# test2.net
KiCad netlist of a schematic drawn in EAGLE
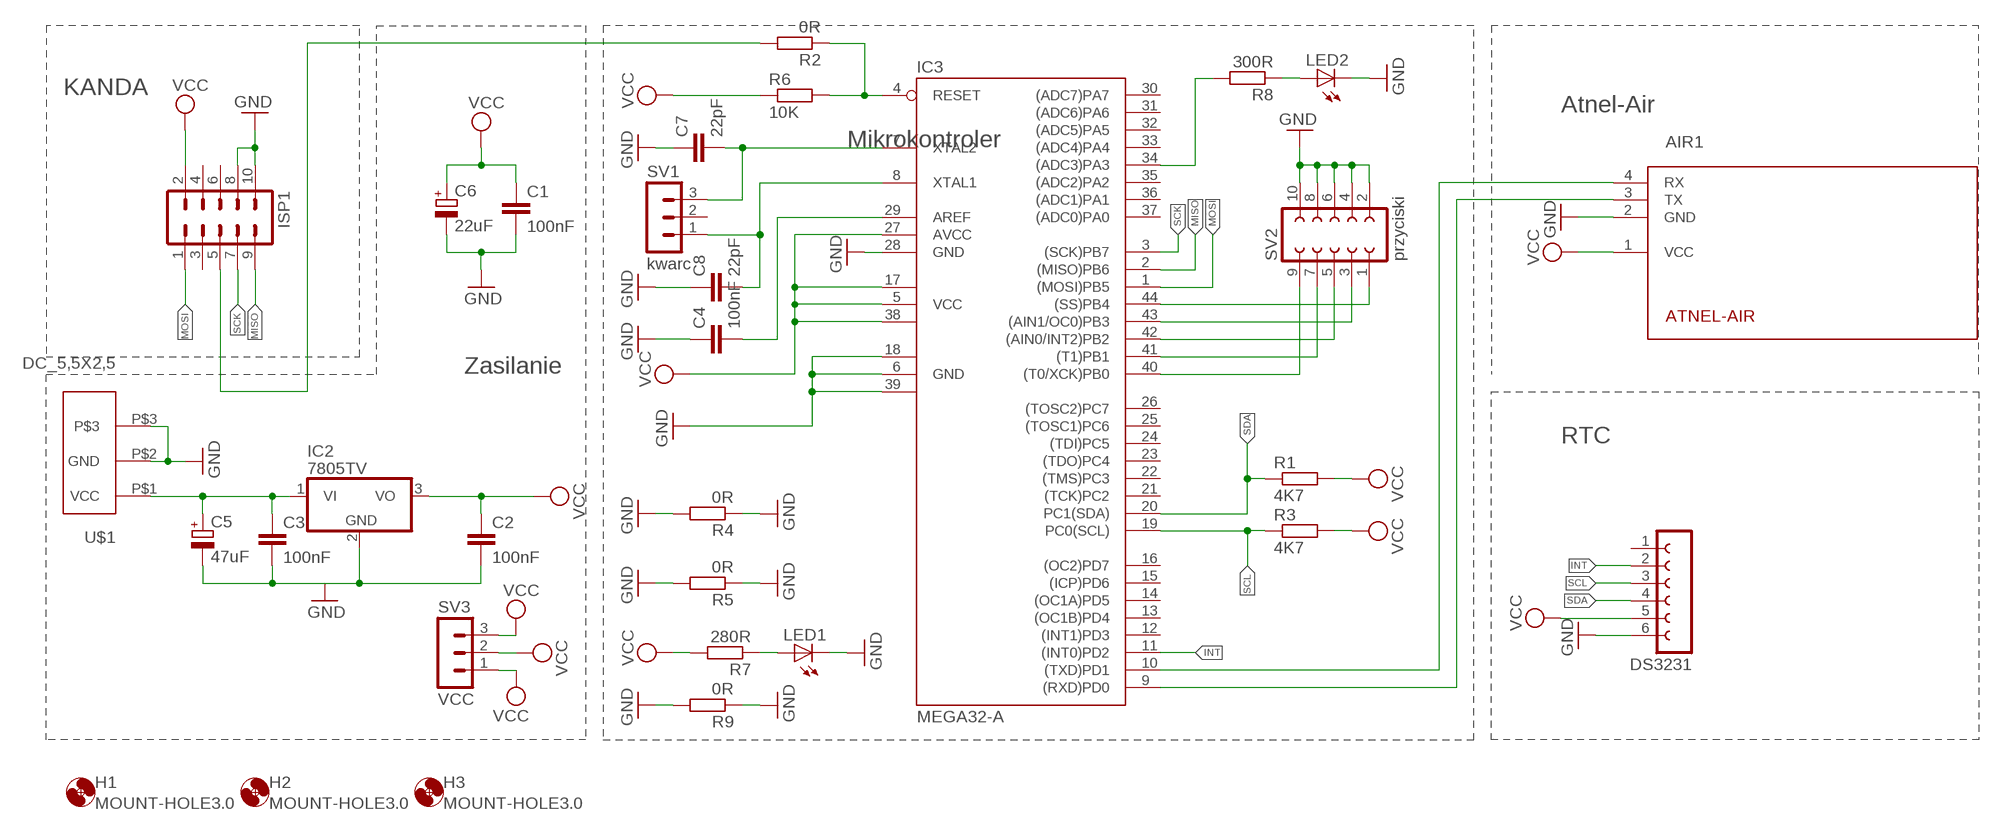
[diagram p0: schematic, sheet 1]

(export (version "E")
  (design (tool "Eeschema 10.0.6"))
  (components
    (comp (ref "AIR1")
      (value "ATNEL-AIR")
      (footprint "eagle-import:ATNEL-AIR")
      (libsource (lib "eagle-import") (part "ATNEL-AIR"))
    )
    (comp (ref "C1")
      (value "100nF")
      (footprint "eagle-import:C025-024X044")
      (libsource (lib "eagle-import") (part "C-EU025-024X044"))
    )
    (comp (ref "C2")
      (value "100nF")
      (footprint "eagle-import:C025-024X044")
      (libsource (lib "eagle-import") (part "C-EU025-024X044"))
    )
    (comp (ref "C3")
      (value "100nF")
      (footprint "eagle-import:C025-024X044")
      (libsource (lib "eagle-import") (part "C-EU025-024X044"))
    )
    (comp (ref "C4")
      (value "100nF")
      (footprint "eagle-import:C025-024X044")
      (libsource (lib "eagle-import") (part "C-EU025-024X044"))
    )
    (comp (ref "C5")
      (value "47uF")
      (footprint "eagle-import:B45181A")
      (libsource (lib "eagle-import") (part "CPOL-EUB45181A"))
    )
    (comp (ref "C6")
      (value "22uF")
      (footprint "eagle-import:B45181A")
      (libsource (lib "eagle-import") (part "CPOL-EUB45181A"))
    )
    (comp (ref "C7")
      (value "22pF")
      (footprint "eagle-import:C025-024X044")
      (libsource (lib "eagle-import") (part "C-EU025-024X044"))
    )
    (comp (ref "C8")
      (value "22pF")
      (footprint "eagle-import:C025-024X044")
      (libsource (lib "eagle-import") (part "C-EU025-024X044"))
    )
    (comp (ref "DS3231")
      (value "FE06-1")
      (footprint "eagle-import:FE06")
      (libsource (lib "eagle-import") (part "FE06-1"))
    )
    (comp (ref "H1")
      (value "MOUNT-HOLE3.0")
      (footprint "eagle-import:3,0")
      (libsource (lib "eagle-import") (part "MOUNT-HOLE3.0"))
    )
    (comp (ref "H2")
      (value "MOUNT-HOLE3.0")
      (footprint "eagle-import:3,0")
      (libsource (lib "eagle-import") (part "MOUNT-HOLE3.0"))
    )
    (comp (ref "H3")
      (value "MOUNT-HOLE3.0")
      (footprint "eagle-import:3,0")
      (libsource (lib "eagle-import") (part "MOUNT-HOLE3.0"))
    )
    (comp (ref "IC2")
      (value "7805TV")
      (footprint "eagle-import:TO220V")
      (libsource (lib "eagle-import") (part "78TV05"))
    )
    (comp (ref "IC3")
      (value "MEGA32-A")
      (footprint "eagle-import:TQFP44")
      (fields (field (name "MPN") "ATMEGA32-16AU"))
      (libsource (lib "eagle-import") (part "MEGA32-A"))
    )
    (comp (ref "ISP1")
      (value "ML10")
      (footprint "eagle-import:ML10")
      (libsource (lib "eagle-import") (part "ML10"))
    )
    (comp (ref "LED1")
      (value "LED5MM")
      (footprint "eagle-import:LED5MM")
      (libsource (lib "eagle-import") (part "LED5MM"))
    )
    (comp (ref "LED2")
      (value "LED5MM")
      (footprint "eagle-import:LED5MM")
      (libsource (lib "eagle-import") (part "LED5MM"))
    )
    (comp (ref "R1")
      (value "4K7")
      (footprint "eagle-import:R1206W")
      (libsource (lib "eagle-import") (part "R-EU_R1206W"))
    )
    (comp (ref "R2")
      (value "0R")
      (footprint "eagle-import:R1206W")
      (libsource (lib "eagle-import") (part "R-EU_R1206W"))
    )
    (comp (ref "R3")
      (value "4K7")
      (footprint "eagle-import:R1206W")
      (libsource (lib "eagle-import") (part "R-EU_R1206W"))
    )
    (comp (ref "R4")
      (value "0R")
      (footprint "eagle-import:R1206W")
      (libsource (lib "eagle-import") (part "R-EU_R1206W"))
    )
    (comp (ref "R5")
      (value "0R")
      (footprint "eagle-import:R1206W")
      (libsource (lib "eagle-import") (part "R-EU_R1206W"))
    )
    (comp (ref "R6")
      (value "10K")
      (footprint "eagle-import:R1206W")
      (libsource (lib "eagle-import") (part "R-EU_R1206W"))
    )
    (comp (ref "R7")
      (value "280R")
      (footprint "eagle-import:R1206W")
      (libsource (lib "eagle-import") (part "R-EU_R1206W"))
    )
    (comp (ref "R8")
      (value "300R")
      (footprint "eagle-import:R1206W")
      (libsource (lib "eagle-import") (part "R-EU_R1206W"))
    )
    (comp (ref "R9")
      (value "0R")
      (footprint "eagle-import:R1206W")
      (libsource (lib "eagle-import") (part "R-EU_R1206W"))
    )
    (comp (ref "SV1")
      (value "kwarc")
      (footprint "eagle-import:MA03-1")
      (libsource (lib "eagle-import") (part "MA03-1"))
    )
    (comp (ref "SV2")
      (value "przyciski")
      (footprint "eagle-import:FE05-2")
      (libsource (lib "eagle-import") (part "FE05-2"))
    )
    (comp (ref "SV3")
      (value "VCC")
      (footprint "eagle-import:MA03-1")
      (libsource (lib "eagle-import") (part "MA03-1"))
    )
    (comp (ref "U$1")
      (value "DC_5,5X2,5")
      (footprint "eagle-import:DC_5,5X2,5")
      (libsource (lib "eagle-import") (part "DC_5,5X2,5"))
    )
  )
  (nets
    (net (code "1") (name "/RST") (class "Default")
      (node (ref "IC3") (pin "4") (pinfunction "RESET_4") (pintype "input"))
      (node (ref "ISP1") (pin "5") (pinfunction "5_5") (pintype "passive"))
      (node (ref "R2") (pin "1") (pinfunction "1_1") (pintype "passive"))
      (node (ref "R2") (pin "2") (pinfunction "2_2") (pintype "passive"))
      (node (ref "R6") (pin "2") (pinfunction "2_2") (pintype "passive"))
    )
    (net (code "2") (name "GND") (class "Default")
      (node (ref "AIR1") (pin "2") (pinfunction "GND_2") (pintype "bidirectional"))
      (node (ref "C1") (pin "2") (pinfunction "2_2") (pintype "passive"))
      (node (ref "C2") (pin "2") (pinfunction "2_2") (pintype "passive"))
      (node (ref "C3") (pin "2") (pinfunction "2_2") (pintype "passive"))
      (node (ref "C4") (pin "1") (pinfunction "1_1") (pintype "passive"))
      (node (ref "C5") (pin "-") (pinfunction "-_-") (pintype "passive"))
      (node (ref "C6") (pin "-") (pinfunction "-_-") (pintype "passive"))
      (node (ref "C7") (pin "1") (pinfunction "1_1") (pintype "passive"))
      (node (ref "C8") (pin "1") (pinfunction "1_1") (pintype "passive"))
      (node (ref "DS3231") (pin "6") (pinfunction "6_6") (pintype "passive"))
      (node (ref "IC2") (pin "2") (pinfunction "GND_2") (pintype "passive"))
      (node (ref "IC3") (pin "18") (pinfunction "GND1_18") (pintype "power_in"))
      (node (ref "IC3") (pin "28") (pinfunction "GND_28") (pintype "power_in"))
      (node (ref "IC3") (pin "39") (pinfunction "GND2_39") (pintype "power_in"))
      (node (ref "IC3") (pin "6") (pinfunction "GND_6") (pintype "power_in"))
      (node (ref "ISP1") (pin "10") (pinfunction "10_10") (pintype "passive"))
      (node (ref "ISP1") (pin "8") (pinfunction "8_8") (pintype "passive"))
      (node (ref "LED1") (pin "K") (pinfunction "C_K") (pintype "passive"))
      (node (ref "LED2") (pin "K") (pinfunction "C_K") (pintype "passive"))
      (node (ref "R4") (pin "1") (pinfunction "1_1") (pintype "passive"))
      (node (ref "R4") (pin "2") (pinfunction "2_2") (pintype "passive"))
      (node (ref "R5") (pin "1") (pinfunction "1_1") (pintype "passive"))
      (node (ref "R5") (pin "2") (pinfunction "2_2") (pintype "passive"))
      (node (ref "R9") (pin "1") (pinfunction "1_1") (pintype "passive"))
      (node (ref "R9") (pin "2") (pinfunction "2_2") (pintype "passive"))
      (node (ref "SV2") (pin "10") (pinfunction "10_10") (pintype "passive"))
      (node (ref "SV2") (pin "2") (pinfunction "2_2") (pintype "passive"))
      (node (ref "SV2") (pin "4") (pinfunction "4_4") (pintype "passive"))
      (node (ref "SV2") (pin "6") (pinfunction "6_6") (pintype "passive"))
      (node (ref "SV2") (pin "8") (pinfunction "8_8") (pintype "passive"))
      (node (ref "U$1") (pin "P$2") (pinfunction "GND_P$2") (pintype "bidirectional"))
      (node (ref "U$1") (pin "P$3") (pinfunction "P$3_P$3") (pintype "bidirectional"))
    )
    (net (code "3") (name "INT") (class "Default")
      (node (ref "DS3231") (pin "2") (pinfunction "2_2") (pintype "passive"))
      (node (ref "IC3") (pin "11") (pinfunction "(INT0)PD2_11") (pintype "bidirectional"))
    )
    (net (code "4") (name "MISO") (class "Default")
      (node (ref "IC3") (pin "2") (pinfunction "(MISO)PB6_2") (pintype "bidirectional"))
      (node (ref "ISP1") (pin "9") (pinfunction "9_9") (pintype "passive"))
    )
    (net (code "5") (name "MOSI") (class "Default")
      (node (ref "IC3") (pin "1") (pinfunction "(MOSI)PB5_1") (pintype "bidirectional"))
      (node (ref "ISP1") (pin "1") (pinfunction "1_1") (pintype "passive"))
    )
    (net (code "6") (name "Net-(AIR1-RX)") (class "Default")
      (node (ref "AIR1") (pin "4") (pinfunction "RX_4") (pintype "output"))
      (node (ref "IC3") (pin "10") (pinfunction "(TXD)PD1_10") (pintype "bidirectional"))
    )
    (net (code "7") (name "Net-(AIR1-TX)") (class "Default")
      (node (ref "AIR1") (pin "3") (pinfunction "TX_3") (pintype "input"))
      (node (ref "IC3") (pin "9") (pinfunction "(RXD)PD0_9") (pintype "bidirectional"))
    )
    (net (code "8") (name "Net-(IC2-VI)") (class "Default")
      (node (ref "C3") (pin "1") (pinfunction "1_1") (pintype "passive"))
      (node (ref "C5") (pin "+") (pinfunction "+_+") (pintype "passive"))
      (node (ref "IC2") (pin "1") (pinfunction "VI_1") (pintype "input"))
      (node (ref "U$1") (pin "P$1") (pinfunction "VCC_P$1") (pintype "bidirectional"))
    )
    (net (code "9") (name "Net-(IC3-(ADC3)PA3)") (class "Default")
      (node (ref "IC3") (pin "34") (pinfunction "(ADC3)PA3_34") (pintype "bidirectional"))
      (node (ref "R8") (pin "2") (pinfunction "2_2") (pintype "passive"))
    )
    (net (code "10") (name "Net-(IC3-(AIN0{slash}INT2)PB2)") (class "Default")
      (node (ref "IC3") (pin "42") (pinfunction "(AIN0/INT2)PB2_42") (pintype "bidirectional"))
      (node (ref "SV2") (pin "5") (pinfunction "5_5") (pintype "passive"))
    )
    (net (code "11") (name "Net-(IC3-(AIN1{slash}OC0)PB3)") (class "Default")
      (node (ref "IC3") (pin "43") (pinfunction "(AIN1/OC0)PB3_43") (pintype "bidirectional"))
      (node (ref "SV2") (pin "3") (pinfunction "3_3") (pintype "passive"))
    )
    (net (code "12") (name "Net-(IC3-(SS)PB4)") (class "Default")
      (node (ref "IC3") (pin "44") (pinfunction "(SS)PB4_44") (pintype "bidirectional"))
      (node (ref "SV2") (pin "1") (pinfunction "1_1") (pintype "passive"))
    )
    (net (code "13") (name "Net-(IC3-(T0{slash}XCK)PB0)") (class "Default")
      (node (ref "IC3") (pin "40") (pinfunction "(T0/XCK)PB0_40") (pintype "bidirectional"))
      (node (ref "SV2") (pin "9") (pinfunction "9_9") (pintype "passive"))
    )
    (net (code "14") (name "Net-(IC3-(T1)PB1)") (class "Default")
      (node (ref "IC3") (pin "41") (pinfunction "(T1)PB1_41") (pintype "bidirectional"))
      (node (ref "SV2") (pin "7") (pinfunction "7_7") (pintype "passive"))
    )
    (net (code "15") (name "Net-(IC3-AREF)") (class "Default")
      (node (ref "C4") (pin "2") (pinfunction "2_2") (pintype "passive"))
      (node (ref "IC3") (pin "29") (pinfunction "AREF_29") (pintype "passive"))
    )
    (net (code "16") (name "Net-(IC3-XTAL1)") (class "Default")
      (node (ref "C8") (pin "2") (pinfunction "2_2") (pintype "passive"))
      (node (ref "IC3") (pin "8") (pinfunction "XTAL1_8") (pintype "bidirectional"))
      (node (ref "SV1") (pin "1") (pinfunction "1_1") (pintype "passive"))
    )
    (net (code "17") (name "Net-(IC3-XTAL2)") (class "Default")
      (node (ref "C7") (pin "2") (pinfunction "2_2") (pintype "passive"))
      (node (ref "IC3") (pin "7") (pinfunction "XTAL2_7") (pintype "bidirectional"))
      (node (ref "SV1") (pin "3") (pinfunction "3_3") (pintype "passive"))
    )
    (net (code "18") (name "Net-(LED1-PadA)") (class "Default")
      (node (ref "LED1") (pin "A") (pinfunction "A_A") (pintype "passive"))
      (node (ref "R7") (pin "1") (pinfunction "1_1") (pintype "passive"))
    )
    (net (code "19") (name "Net-(LED2-PadA)") (class "Default")
      (node (ref "LED2") (pin "A") (pinfunction "A_A") (pintype "passive"))
      (node (ref "R8") (pin "1") (pinfunction "1_1") (pintype "passive"))
    )
    (net (code "20") (name "SCK") (class "Default")
      (node (ref "IC3") (pin "3") (pinfunction "(SCK)PB7_3") (pintype "bidirectional"))
      (node (ref "ISP1") (pin "7") (pinfunction "7_7") (pintype "passive"))
    )
    (net (code "21") (name "SCL") (class "Default")
      (node (ref "DS3231") (pin "3") (pinfunction "3_3") (pintype "passive"))
      (node (ref "IC3") (pin "19") (pinfunction "PC0(SCL)_19") (pintype "bidirectional"))
      (node (ref "R3") (pin "1") (pinfunction "1_1") (pintype "passive"))
    )
    (net (code "22") (name "SDA") (class "Default")
      (node (ref "DS3231") (pin "4") (pinfunction "4_4") (pintype "passive"))
      (node (ref "IC3") (pin "20") (pinfunction "PC1(SDA)_20") (pintype "bidirectional"))
      (node (ref "R1") (pin "1") (pinfunction "1_1") (pintype "passive"))
    )
    (net (code "23") (name "VCC") (class "Default")
      (node (ref "AIR1") (pin "1") (pinfunction "VCC_1") (pintype "bidirectional"))
      (node (ref "C1") (pin "1") (pinfunction "1_1") (pintype "passive"))
      (node (ref "C2") (pin "1") (pinfunction "1_1") (pintype "passive"))
      (node (ref "C6") (pin "+") (pinfunction "+_+") (pintype "passive"))
      (node (ref "DS3231") (pin "5") (pinfunction "5_5") (pintype "passive"))
      (node (ref "IC2") (pin "3") (pinfunction "VO_3") (pintype "passive"))
      (node (ref "IC3") (pin "17") (pinfunction "VCC1_17") (pintype "power_in"))
      (node (ref "IC3") (pin "27") (pinfunction "AVCC_27") (pintype "power_in"))
      (node (ref "IC3") (pin "38") (pinfunction "VCC2_38") (pintype "power_in"))
      (node (ref "IC3") (pin "5") (pinfunction "VCC_5") (pintype "power_in"))
      (node (ref "ISP1") (pin "2") (pinfunction "2_2") (pintype "passive"))
      (node (ref "R1") (pin "2") (pinfunction "2_2") (pintype "passive"))
      (node (ref "R3") (pin "2") (pinfunction "2_2") (pintype "passive"))
      (node (ref "R6") (pin "1") (pinfunction "1_1") (pintype "passive"))
      (node (ref "R7") (pin "2") (pinfunction "2_2") (pintype "passive"))
      (node (ref "SV3") (pin "1") (pinfunction "1_1") (pintype "passive"))
      (node (ref "SV3") (pin "2") (pinfunction "2_2") (pintype "passive"))
      (node (ref "SV3") (pin "3") (pinfunction "3_3") (pintype "passive"))
    )
    (net (code "24") (name "unconnected-(DS3231-Pad1)") (class "Default")
      (node (ref "DS3231") (pin "1") (pinfunction "1_1") (pintype "passive"))
    )
    (net (code "25") (name "unconnected-(IC3-(ADC0)PA0-Pad37)") (class "Default")
      (node (ref "IC3") (pin "37") (pinfunction "(ADC0)PA0_37") (pintype "bidirectional"))
    )
    (net (code "26") (name "unconnected-(IC3-(ADC1)PA1-Pad36)") (class "Default")
      (node (ref "IC3") (pin "36") (pinfunction "(ADC1)PA1_36") (pintype "bidirectional"))
    )
    (net (code "27") (name "unconnected-(IC3-(ADC2)PA2-Pad35)") (class "Default")
      (node (ref "IC3") (pin "35") (pinfunction "(ADC2)PA2_35") (pintype "bidirectional"))
    )
    (net (code "28") (name "unconnected-(IC3-(ADC4)PA4-Pad33)") (class "Default")
      (node (ref "IC3") (pin "33") (pinfunction "(ADC4)PA4_33") (pintype "bidirectional"))
    )
    (net (code "29") (name "unconnected-(IC3-(ADC5)PA5-Pad32)") (class "Default")
      (node (ref "IC3") (pin "32") (pinfunction "(ADC5)PA5_32") (pintype "bidirectional"))
    )
    (net (code "30") (name "unconnected-(IC3-(ADC6)PA6-Pad31)") (class "Default")
      (node (ref "IC3") (pin "31") (pinfunction "(ADC6)PA6_31") (pintype "bidirectional"))
    )
    (net (code "31") (name "unconnected-(IC3-(ADC7)PA7-Pad30)") (class "Default")
      (node (ref "IC3") (pin "30") (pinfunction "(ADC7)PA7_30") (pintype "bidirectional"))
    )
    (net (code "32") (name "unconnected-(IC3-(ICP)PD6-Pad15)") (class "Default")
      (node (ref "IC3") (pin "15") (pinfunction "(ICP)PD6_15") (pintype "bidirectional"))
    )
    (net (code "33") (name "unconnected-(IC3-(INT1)PD3-Pad12)") (class "Default")
      (node (ref "IC3") (pin "12") (pinfunction "(INT1)PD3_12") (pintype "bidirectional"))
    )
    (net (code "34") (name "unconnected-(IC3-(OC1A)PD5-Pad14)") (class "Default")
      (node (ref "IC3") (pin "14") (pinfunction "(OC1A)PD5_14") (pintype "bidirectional"))
    )
    (net (code "35") (name "unconnected-(IC3-(OC1B)PD4-Pad13)") (class "Default")
      (node (ref "IC3") (pin "13") (pinfunction "(OC1B)PD4_13") (pintype "bidirectional"))
    )
    (net (code "36") (name "unconnected-(IC3-(OC2)PD7-Pad16)") (class "Default")
      (node (ref "IC3") (pin "16") (pinfunction "(OC2)PD7_16") (pintype "bidirectional"))
    )
    (net (code "37") (name "unconnected-(IC3-(TCK)PC2-Pad21)") (class "Default")
      (node (ref "IC3") (pin "21") (pinfunction "(TCK)PC2_21") (pintype "bidirectional"))
    )
    (net (code "38") (name "unconnected-(IC3-(TDI)PC5-Pad24)") (class "Default")
      (node (ref "IC3") (pin "24") (pinfunction "(TDI)PC5_24") (pintype "bidirectional"))
    )
    (net (code "39") (name "unconnected-(IC3-(TDO)PC4-Pad23)") (class "Default")
      (node (ref "IC3") (pin "23") (pinfunction "(TDO)PC4_23") (pintype "bidirectional"))
    )
    (net (code "40") (name "unconnected-(IC3-(TMS)PC3-Pad22)") (class "Default")
      (node (ref "IC3") (pin "22") (pinfunction "(TMS)PC3_22") (pintype "bidirectional"))
    )
    (net (code "41") (name "unconnected-(IC3-(TOSC1)PC6-Pad25)") (class "Default")
      (node (ref "IC3") (pin "25") (pinfunction "(TOSC1)PC6_25") (pintype "bidirectional"))
    )
    (net (code "42") (name "unconnected-(IC3-(TOSC2)PC7-Pad26)") (class "Default")
      (node (ref "IC3") (pin "26") (pinfunction "(TOSC2)PC7_26") (pintype "bidirectional"))
    )
    (net (code "43") (name "unconnected-(ISP1-Pad3)") (class "Default")
      (node (ref "ISP1") (pin "3") (pinfunction "3_3") (pintype "passive"))
    )
    (net (code "44") (name "unconnected-(ISP1-Pad4)") (class "Default")
      (node (ref "ISP1") (pin "4") (pinfunction "4_4") (pintype "passive"))
    )
    (net (code "45") (name "unconnected-(ISP1-Pad6)") (class "Default")
      (node (ref "ISP1") (pin "6") (pinfunction "6_6") (pintype "passive"))
    )
    (net (code "46") (name "unconnected-(SV1-Pad2)") (class "Default")
      (node (ref "SV1") (pin "2") (pinfunction "2_2") (pintype "passive"))
    )
  )
)
